# Batterycharger.net
KiCad netlist of a schematic drawn in Altium Designer
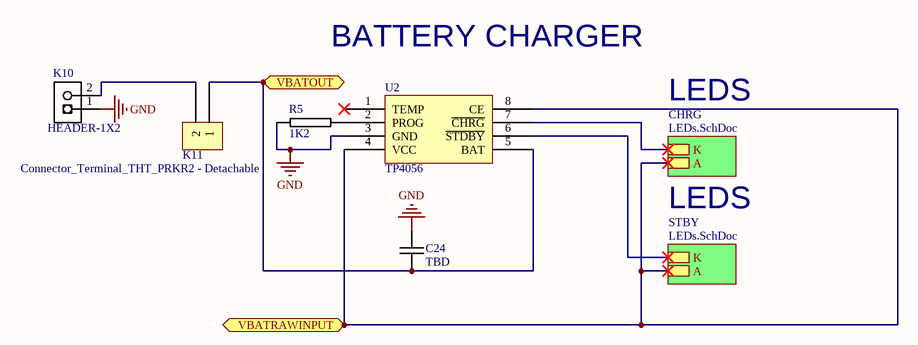
[diagram p0: Batterycharger.SchDoc]

(export (version "E")
  (design (tool "Eeschema 10.0.6"))
  (components
    (comp (ref "C24")
      (value "TBD")
      (footprint "1210C-GENERIC")
      (description "CAPACITOR 1210 CERAMIC VALUE TO BE DETERMINED")
      (libsource (lib "RVA_Altium_Library") (part "Passives_Capacitors_1210_1210C-TBD"))
    )
    (comp (ref "K10")
      (value "HEADER-1X2")
      (footprint "HEADER-1X2")
      (libsource (lib "RVA_Altium_Library") (part "HEADER-1X2"))
    )
    (comp (ref "K11")
      (value "Connector_Terminal_THT_PRKR2 - Detachable")
      (footprint "PRKR2-DET")
      (libsource (lib "RVA_Altium_Library") (part "Connector_Terminal_THT_PRKR2 - Detachable"))
    )
    (comp (ref "R5")
      (value "1K2")
      (footprint "0603R-GENERIC")
      (description "GENERIC RESISTOR 0603")
      (fields
        (field (name "MANUFACTURER PART NUMBER") "RMCF 1/16 1.2K 1% R")
        (field (name "MANUFACTURER") "Stackpole Electronics Inc")
      )
      (libsource (lib "RVA_Altium_Library") (part "0603R-1K2"))
    )
    (comp (ref "U2")
      (value "TP4056")
      (footprint "SO8_N")
      (libsource (lib "RVA_Altium_Library") (part "TP4056"))
    )
  )
  (nets
    (net (code "1") (name "/K") (class "Default")
      (node (ref "U2") (pin "6") (pinfunction "~{STDBY}_6") (pintype "passive+no_connect"))
    )
    (net (code "2") (name "/K_1") (class "Default")
      (node (ref "U2") (pin "7") (pinfunction "~{CHRG}_7") (pintype "passive+no_connect"))
    )
    (net (code "3") (name "/VBATOUT") (class "Default")
      (node (ref "C24") (pin "2") (pintype "passive"))
      (node (ref "K11") (pin "1") (pinfunction "1_1") (pintype "passive"))
      (node (ref "U2") (pin "5") (pinfunction "BAT_5") (pintype "passive"))
    )
    (net (code "4") (name "/VBATRAWINPUT") (class "Default")
      (node (ref "U2") (pin "4") (pinfunction "VCC_4") (pintype "passive"))
      (node (ref "U2") (pin "8") (pinfunction "CE_8") (pintype "passive"))
    )
    (net (code "5") (name "GND") (class "Default")
      (node (ref "C24") (pin "1") (pintype "passive"))
      (node (ref "K10") (pin "1") (pintype "passive"))
      (node (ref "R5") (pin "1") (pintype "passive"))
      (node (ref "U2") (pin "3") (pinfunction "GND_3") (pintype "passive"))
    )
    (net (code "6") (name "Net-(K10-Pad2)") (class "Default")
      (node (ref "K10") (pin "2") (pintype "passive"))
      (node (ref "K11") (pin "2") (pinfunction "2_2") (pintype "passive"))
    )
    (net (code "7") (name "Net-(U2-PROG)") (class "Default")
      (node (ref "R5") (pin "2") (pintype "passive"))
      (node (ref "U2") (pin "2") (pinfunction "PROG_2") (pintype "passive"))
    )
    (net (code "8") (name "unconnected-(U2-TEMP-Pad1)") (class "Default")
      (node (ref "U2") (pin "1") (pinfunction "TEMP_1") (pintype "passive+no_connect"))
    )
  )
)
